# Control-MCU.net
KiCad netlist of a schematic drawn in Altium Designer
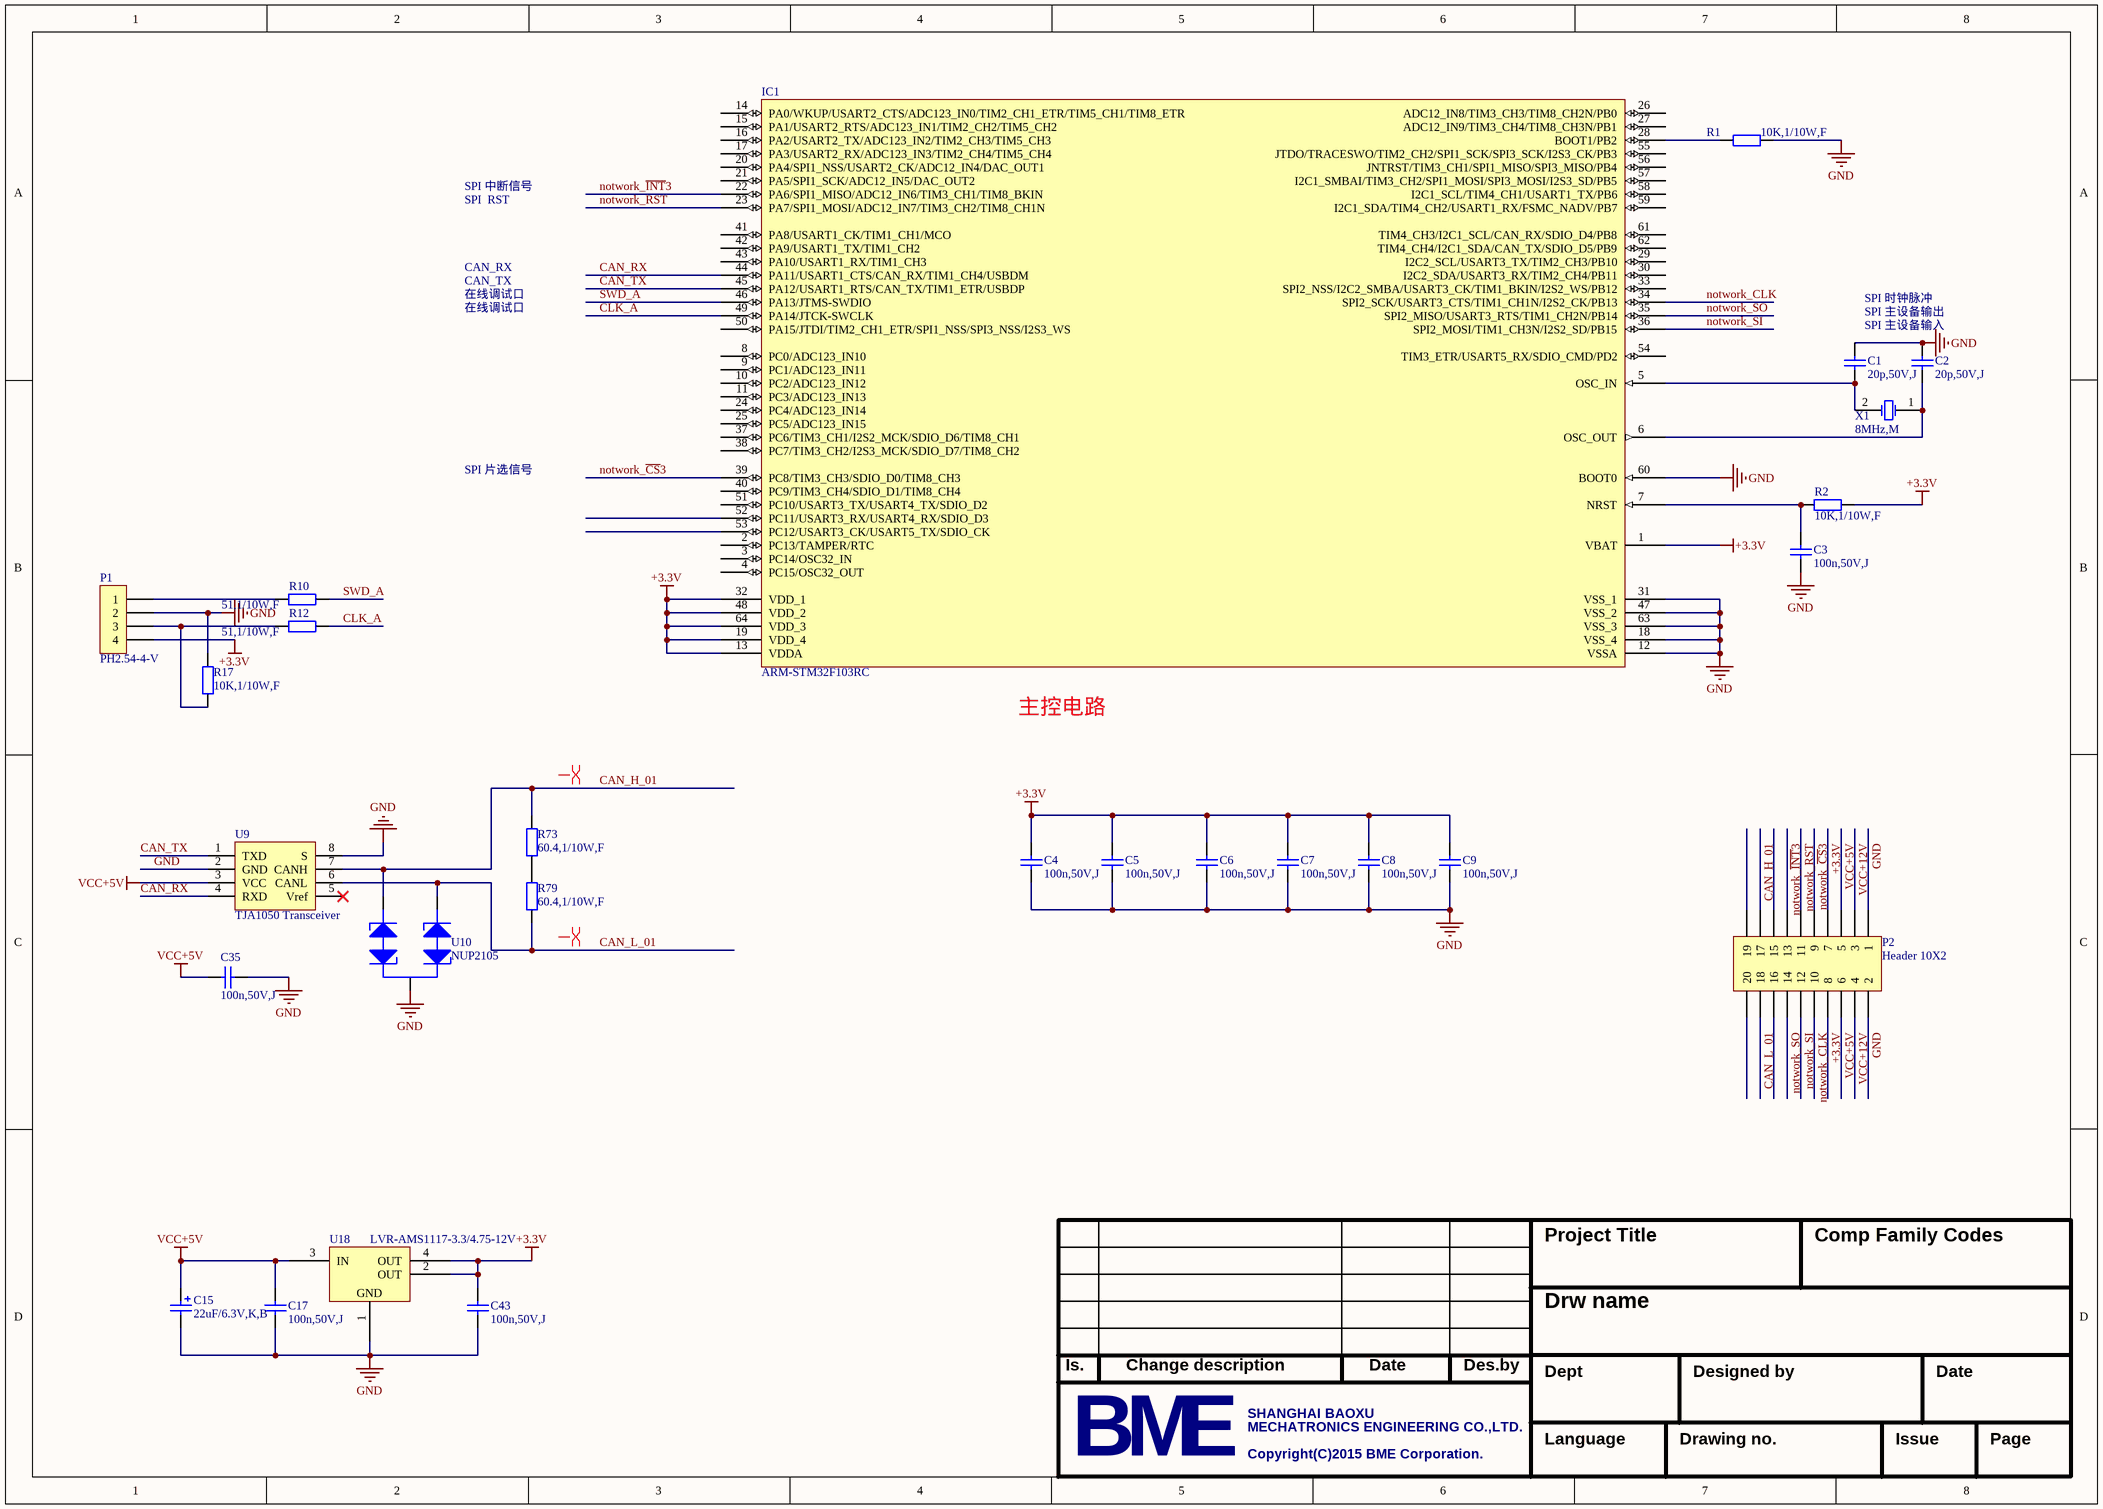
[diagram p0: Control-MCU.SchDoc]

(export (version "E")
  (design (tool "Eeschema 10.0.6"))
  (components
    (comp (ref "C1")
      (value "20p,50V,J")
      (footprint "C0603")
      (fields (field (name "PART NUMBER") "30602019"))
      (libsource (lib "KNLK-Chip Capacitors") (part "30602019"))
    )
    (comp (ref "C2")
      (value "20p,50V,J")
      (footprint "C0603")
      (fields (field (name "PART NUMBER") "30602019"))
      (libsource (lib "KNLK-Chip Capacitors") (part "30602019"))
    )
    (comp (ref "C3")
      (value "100n,50V,J")
      (footprint "C0603")
      (fields (field (name "PART NUMBER") "30602059"))
      (libsource (lib "KNLK-Chip Capacitors") (part "30602059"))
    )
    (comp (ref "C4")
      (value "100n,50V,J")
      (footprint "C0603")
      (fields (field (name "PART NUMBER") "30602059"))
      (libsource (lib "KNLK-Chip Capacitors") (part "30602059"))
    )
    (comp (ref "C5")
      (value "100n,50V,J")
      (footprint "C0603")
      (fields (field (name "PART NUMBER") "30602059"))
      (libsource (lib "KNLK-Chip Capacitors") (part "30602059"))
    )
    (comp (ref "C6")
      (value "100n,50V,J")
      (footprint "C0603")
      (fields (field (name "PART NUMBER") "30602059"))
      (libsource (lib "KNLK-Chip Capacitors") (part "30602059"))
    )
    (comp (ref "C7")
      (value "100n,50V,J")
      (footprint "C0603")
      (fields (field (name "PART NUMBER") "30602059"))
      (libsource (lib "KNLK-Chip Capacitors") (part "30602059"))
    )
    (comp (ref "C8")
      (value "100n,50V,J")
      (footprint "C0603")
      (fields (field (name "PART NUMBER") "30602059"))
      (libsource (lib "KNLK-Chip Capacitors") (part "30602059"))
    )
    (comp (ref "C9")
      (value "100n,50V,J")
      (footprint "C0603")
      (fields (field (name "PART NUMBER") "30602059"))
      (libsource (lib "KNLK-Chip Capacitors") (part "30602059"))
    )
    (comp (ref "C15")
      (value "22uF/6.3V,K,B")
      (footprint "3528B")
      (fields (field (name "PART NUMBER") "30603403"))
      (libsource (lib "KNLK-Tantalum Capacitor") (part "30603403"))
    )
    (comp (ref "C17")
      (value "100n,50V,J")
      (footprint "C0603")
      (fields (field (name "PART NUMBER") "30602059"))
      (libsource (lib "KNLK-Chip Capacitors") (part "30602059"))
    )
    (comp (ref "C35")
      (value "100n,50V,J")
      (footprint "C0603")
      (fields (field (name "PART NUMBER") "30602059"))
      (libsource (lib "KNLK-Chip Capacitors") (part "30602059"))
    )
    (comp (ref "C43")
      (value "100n,50V,J")
      (footprint "C0603")
      (fields (field (name "PART NUMBER") "30602059"))
      (libsource (lib "KNLK-Chip Capacitors") (part "30602059"))
    )
    (comp (ref "IC1")
      (value "ARM-STM32F103RC")
      (footprint "LQFP-64")
      (fields (field (name "PART NUMBER") "30613205"))
      (libsource (lib "KNLK-SMT chip") (part "30613205"))
    )
    (comp (ref "P1")
      (value "PH2.54-4-V")
      (footprint "SIP4")
      (fields (field (name "PART NUMBER") "30609103"))
      (libsource (lib "KNLK-Interface") (part "30609103"))
    )
    (comp (ref "P2")
      (value "Header 10X2")
      (footprint "805-1")
      (description "Header, 10-Pin, Dual row")
      (fields (field (name "PUBLISHER") "Altium Limited"))
      (libsource (lib "Miscellaneous Connectors") (part "Header 10X2"))
    )
    (comp (ref "R1")
      (value "10K,1/10W,F")
      (footprint "R0603")
      (fields (field (name "PART NUMBER") "30601099"))
      (libsource (lib "KNLK-Chip Resistor") (part "30601099"))
    )
    (comp (ref "R2")
      (value "10K,1/10W,F")
      (footprint "R0603")
      (fields (field (name "PART NUMBER") "30601099"))
      (libsource (lib "KNLK-Chip Resistor") (part "30601099"))
    )
    (comp (ref "R10")
      (value "51,1/10W,F")
      (footprint "R0603")
      (fields (field (name "PART NUMBER") "30601043"))
      (libsource (lib "KNLK-Chip Resistor") (part "30601043"))
    )
    (comp (ref "R12")
      (value "51,1/10W,F")
      (footprint "R0603")
      (fields (field (name "PART NUMBER") "30601043"))
      (libsource (lib "KNLK-Chip Resistor") (part "30601043"))
    )
    (comp (ref "R17")
      (value "10K,1/10W,F")
      (footprint "R0603")
      (fields (field (name "PART NUMBER") "30601099"))
      (libsource (lib "") (part "30601099_1"))
    )
    (comp (ref "R73")
      (value "60.4,1/10W,F")
      (footprint "R0603")
      (fields (field (name "PART NUMBER") "30601045"))
      (libsource (lib "KNLK-Chip Resistor") (part "30601045"))
    )
    (comp (ref "R79")
      (value "60.4,1/10W,F")
      (footprint "R0603")
      (fields (field (name "PART NUMBER") "30601045"))
      (libsource (lib "KNLK-Chip Resistor") (part "30601045"))
    )
    (comp (ref "U9")
      (value "TJA1050 Transceiver")
      (footprint "SOP-8")
      (fields (field (name "PART NUMBER") "30613501"))
      (libsource (lib "KNLK-SMT chip") (part "30613501"))
    )
    (comp (ref "U10")
      (value "NUP2105")
      (footprint "SOT-23P")
      (fields (field (name "PART NUMBER") "30613517"))
      (libsource (lib "KNLK-SMT chip") (part "30613517"))
    )
    (comp (ref "U18")
      (value "LVR-AMS1117-3.3/4.75-12V")
      (footprint "SOT-223")
      (fields (field (name "PART NUMBER") "30614001"))
      (libsource (lib "KNLK-Power supply chip") (part "30614001"))
    )
    (comp (ref "X1")
      (value "8MHz,M")
      (footprint "X5032")
      (fields (field (name "PART NUMBER") "30612002"))
      (libsource (lib "KNLK-CrystalOscillator") (part "30612002"))
    )
  )
  (nets
    (net (code "1") (name "+3.3V") (class "Default")
      (node (ref "C4") (pin "2") (pinfunction "2_2") (pintype "passive"))
      (node (ref "C43") (pin "1") (pinfunction "1_1") (pintype "passive"))
      (node (ref "C5") (pin "2") (pinfunction "2_2") (pintype "passive"))
      (node (ref "C6") (pin "2") (pinfunction "2_2") (pintype "passive"))
      (node (ref "C7") (pin "2") (pinfunction "2_2") (pintype "passive"))
      (node (ref "C8") (pin "2") (pinfunction "2_2") (pintype "passive"))
      (node (ref "C9") (pin "2") (pinfunction "2_2") (pintype "passive"))
      (node (ref "IC1") (pin "1") (pinfunction "VBAT_1") (pintype "power_in"))
      (node (ref "IC1") (pin "13") (pinfunction "VDDA_13") (pintype "power_in"))
      (node (ref "IC1") (pin "19") (pinfunction "VDD_4_19") (pintype "power_in"))
      (node (ref "IC1") (pin "32") (pinfunction "VDD_1_32") (pintype "power_in"))
      (node (ref "IC1") (pin "48") (pinfunction "VDD_2_48") (pintype "power_in"))
      (node (ref "IC1") (pin "64") (pinfunction "VDD_3_64") (pintype "power_in"))
      (node (ref "P1") (pin "4") (pinfunction "4_4") (pintype "passive"))
      (node (ref "P2") (pin "7") (pinfunction "7_7") (pintype "passive"))
      (node (ref "P2") (pin "8") (pinfunction "8_8") (pintype "passive"))
      (node (ref "R2") (pin "1") (pinfunction "1_1") (pintype "passive"))
      (node (ref "U18") (pin "2") (pinfunction "OUT_2") (pintype "passive"))
      (node (ref "U18") (pin "4") (pinfunction "OUT_4") (pintype "passive"))
    )
    (net (code "2") (name "/CAN_H_01") (class "Default")
      (node (ref "P2") (pin "17") (pinfunction "17_17") (pintype "passive"))
      (node (ref "R73") (pin "2") (pinfunction "2_2") (pintype "passive"))
      (node (ref "U10") (pin "1") (pinfunction "1_1") (pintype "passive"))
      (node (ref "U9") (pin "7") (pinfunction "CANH_7") (pintype "passive"))
    )
    (net (code "3") (name "/CAN_L_01") (class "Default")
      (node (ref "P2") (pin "18") (pinfunction "18_18") (pintype "passive"))
      (node (ref "R79") (pin "1") (pinfunction "1_1") (pintype "passive"))
      (node (ref "U10") (pin "2") (pinfunction "2_2") (pintype "passive"))
      (node (ref "U9") (pin "6") (pinfunction "CANL_6") (pintype "passive"))
    )
    (net (code "4") (name "/CAN_RX") (class "Default")
      (node (ref "IC1") (pin "44") (pinfunction "PA11/USART1_CTS/CAN_RX/TIM1_CH4/USBDM_44") (pintype "bidirectional"))
      (node (ref "U9") (pin "4") (pinfunction "RXD_4") (pintype "passive"))
    )
    (net (code "5") (name "/CAN_TX") (class "Default")
      (node (ref "IC1") (pin "45") (pinfunction "PA12/USART1_RTS/CAN_TX/TIM1_ETR/USBDP_45") (pintype "bidirectional"))
      (node (ref "U9") (pin "1") (pinfunction "TXD_1") (pintype "passive"))
    )
    (net (code "6") (name "/CLK_A") (class "Default")
      (node (ref "IC1") (pin "49") (pinfunction "PA14/JTCK-SWCLK_49") (pintype "bidirectional"))
      (node (ref "R12") (pin "2") (pinfunction "2_2") (pintype "passive"))
    )
    (net (code "7") (name "/SWD_A") (class "Default")
      (node (ref "IC1") (pin "46") (pinfunction "PA13/JTMS-SWDIO_46") (pintype "bidirectional"))
      (node (ref "R10") (pin "2") (pinfunction "2_2") (pintype "passive"))
    )
    (net (code "8") (name "/VCC+12V") (class "Default")
      (node (ref "P2") (pin "3") (pinfunction "3_3") (pintype "passive"))
      (node (ref "P2") (pin "4") (pinfunction "4_4") (pintype "passive"))
    )
    (net (code "9") (name "/notwork_CLK") (class "Default")
      (node (ref "IC1") (pin "34") (pinfunction "SPI2_SCK/USART3_CTS/TIM1_CH1N/I2S2_CK/PB13_34") (pintype "bidirectional"))
      (node (ref "P2") (pin "10") (pinfunction "10_10") (pintype "passive"))
    )
    (net (code "10") (name "/notwork_RST") (class "Default")
      (node (ref "IC1") (pin "23") (pinfunction "PA7/SPI1_MOSI/ADC12_IN7/TIM3_CH2/TIM8_CH1N_23") (pintype "bidirectional"))
      (node (ref "P2") (pin "11") (pinfunction "11_11") (pintype "passive"))
    )
    (net (code "11") (name "/notwork_SI") (class "Default")
      (node (ref "IC1") (pin "36") (pinfunction "SPI2_MOSI/TIM1_CH3N/I2S2_SD/PB15_36") (pintype "bidirectional"))
      (node (ref "P2") (pin "12") (pinfunction "12_12") (pintype "passive"))
    )
    (net (code "12") (name "/notwork_SO") (class "Default")
      (node (ref "IC1") (pin "35") (pinfunction "SPI2_MISO/USART3_RTS/TIM1_CH2N/PB14_35") (pintype "bidirectional"))
      (node (ref "P2") (pin "14") (pinfunction "14_14") (pintype "passive"))
    )
    (net (code "13") (name "/notwork_~{CS}3") (class "Default")
      (node (ref "IC1") (pin "39") (pinfunction "PC8/TIM3_CH3/SDIO_D0/TIM8_CH3_39") (pintype "bidirectional"))
      (node (ref "P2") (pin "9") (pinfunction "9_9") (pintype "passive"))
    )
    (net (code "14") (name "/notwork_~{INT}3") (class "Default")
      (node (ref "IC1") (pin "22") (pinfunction "PA6/SPI1_MISO/ADC12_IN6/TIM3_CH1/TIM8_BKIN_22") (pintype "bidirectional"))
      (node (ref "P2") (pin "13") (pinfunction "13_13") (pintype "passive"))
    )
    (net (code "15") (name "GND") (class "Default")
      (node (ref "C1") (pin "2") (pinfunction "2_2") (pintype "passive"))
      (node (ref "C15") (pin "2") (pinfunction "2_2") (pintype "passive"))
      (node (ref "C17") (pin "2") (pinfunction "2_2") (pintype "passive"))
      (node (ref "C2") (pin "2") (pinfunction "2_2") (pintype "passive"))
      (node (ref "C3") (pin "1") (pinfunction "1_1") (pintype "passive"))
      (node (ref "C35") (pin "1") (pinfunction "1_1") (pintype "passive"))
      (node (ref "C4") (pin "1") (pinfunction "1_1") (pintype "passive"))
      (node (ref "C43") (pin "2") (pinfunction "2_2") (pintype "passive"))
      (node (ref "C5") (pin "1") (pinfunction "1_1") (pintype "passive"))
      (node (ref "C6") (pin "1") (pinfunction "1_1") (pintype "passive"))
      (node (ref "C7") (pin "1") (pinfunction "1_1") (pintype "passive"))
      (node (ref "C8") (pin "1") (pinfunction "1_1") (pintype "passive"))
      (node (ref "C9") (pin "1") (pinfunction "1_1") (pintype "passive"))
      (node (ref "IC1") (pin "12") (pinfunction "VSSA_12") (pintype "power_in"))
      (node (ref "IC1") (pin "18") (pinfunction "VSS_4_18") (pintype "power_in"))
      (node (ref "IC1") (pin "31") (pinfunction "VSS_1_31") (pintype "power_in"))
      (node (ref "IC1") (pin "47") (pinfunction "VSS_2_47") (pintype "power_in"))
      (node (ref "IC1") (pin "60") (pinfunction "BOOT0_60") (pintype "input"))
      (node (ref "IC1") (pin "63") (pinfunction "VSS_3_63") (pintype "power_in"))
      (node (ref "P1") (pin "2") (pinfunction "2_2") (pintype "passive"))
      (node (ref "P2") (pin "1") (pinfunction "1_1") (pintype "passive"))
      (node (ref "P2") (pin "2") (pinfunction "2_2") (pintype "passive"))
      (node (ref "R1") (pin "1") (pinfunction "1_1") (pintype "passive"))
      (node (ref "R17") (pin "1") (pinfunction "1_1") (pintype "passive"))
      (node (ref "U10") (pin "3") (pinfunction "3_3") (pintype "passive"))
      (node (ref "U18") (pin "1") (pinfunction "GND_1") (pintype "passive"))
      (node (ref "U9") (pin "2") (pinfunction "GND_2") (pintype "passive"))
      (node (ref "U9") (pin "8") (pinfunction "S_8") (pintype "passive"))
    )
    (net (code "16") (name "Net-(IC1-BOOT1{slash}PB2)") (class "Default")
      (node (ref "IC1") (pin "28") (pinfunction "BOOT1/PB2_28") (pintype "bidirectional"))
      (node (ref "R1") (pin "2") (pinfunction "2_2") (pintype "passive"))
    )
    (net (code "17") (name "Net-(IC1-NRST)") (class "Default")
      (node (ref "C3") (pin "2") (pinfunction "2_2") (pintype "passive"))
      (node (ref "IC1") (pin "7") (pinfunction "NRST_7") (pintype "input"))
      (node (ref "R2") (pin "2") (pinfunction "2_2") (pintype "passive"))
    )
    (net (code "18") (name "Net-(IC1-OSC_IN)") (class "Default")
      (node (ref "C1") (pin "1") (pinfunction "1_1") (pintype "passive"))
      (node (ref "IC1") (pin "5") (pinfunction "OSC_IN_5") (pintype "input"))
      (node (ref "X1") (pin "2") (pinfunction "OSC2_2") (pintype "passive"))
    )
    (net (code "19") (name "Net-(IC1-OSC_OUT)") (class "Default")
      (node (ref "C2") (pin "1") (pinfunction "1_1") (pintype "passive"))
      (node (ref "IC1") (pin "6") (pinfunction "OSC_OUT_6") (pintype "output"))
      (node (ref "X1") (pin "1") (pinfunction "OSC1_1") (pintype "passive"))
    )
    (net (code "20") (name "Net-(P1-Pad1)") (class "Default")
      (node (ref "P1") (pin "1") (pinfunction "1_1") (pintype "passive"))
      (node (ref "R10") (pin "1") (pinfunction "1_1") (pintype "passive"))
    )
    (net (code "21") (name "Net-(P1-Pad3)") (class "Default")
      (node (ref "P1") (pin "3") (pinfunction "3_3") (pintype "passive"))
      (node (ref "R12") (pin "1") (pinfunction "1_1") (pintype "passive"))
      (node (ref "R17") (pin "2") (pinfunction "2_2") (pintype "passive"))
    )
    (net (code "22") (name "Net-(R73-Pad1)") (class "Default")
      (node (ref "R73") (pin "1") (pinfunction "1_1") (pintype "passive"))
      (node (ref "R79") (pin "2") (pinfunction "2_2") (pintype "passive"))
    )
    (net (code "23") (name "VCC+5V") (class "Default")
      (node (ref "C15") (pin "1") (pinfunction "1_1") (pintype "passive"))
      (node (ref "C17") (pin "1") (pinfunction "1_1") (pintype "passive"))
      (node (ref "C35") (pin "2") (pinfunction "2_2") (pintype "passive"))
      (node (ref "P2") (pin "5") (pinfunction "5_5") (pintype "passive"))
      (node (ref "P2") (pin "6") (pinfunction "6_6") (pintype "passive"))
      (node (ref "U18") (pin "3") (pinfunction "IN_3") (pintype "passive"))
      (node (ref "U9") (pin "3") (pinfunction "VCC_3") (pintype "passive"))
    )
    (net (code "24") (name "unconnected-(IC1-ADC12_IN8{slash}TIM3_CH3{slash}TIM8_CH2N{slash}PB0-Pad26)") (class "Default")
      (node (ref "IC1") (pin "26") (pinfunction "ADC12_IN8/TIM3_CH3/TIM8_CH2N/PB0_26") (pintype "bidirectional"))
    )
    (net (code "25") (name "unconnected-(IC1-ADC12_IN9{slash}TIM3_CH4{slash}TIM8_CH3N{slash}PB1-Pad27)") (class "Default")
      (node (ref "IC1") (pin "27") (pinfunction "ADC12_IN9/TIM3_CH4/TIM8_CH3N/PB1_27") (pintype "bidirectional"))
    )
    (net (code "26") (name "unconnected-(IC1-I2C1_SCL{slash}TIM4_CH1{slash}USART1_TX{slash}PB6-Pad58)") (class "Default")
      (node (ref "IC1") (pin "58") (pinfunction "I2C1_SCL/TIM4_CH1/USART1_TX/PB6_58") (pintype "bidirectional"))
    )
    (net (code "27") (name "unconnected-(IC1-I2C1_SDA{slash}TIM4_CH2{slash}USART1_RX{slash}FSMC_NADV{slash}PB7-Pad59)") (class "Default")
      (node (ref "IC1") (pin "59") (pinfunction "I2C1_SDA/TIM4_CH2/USART1_RX/FSMC_NADV/PB7_59") (pintype "bidirectional"))
    )
    (net (code "28") (name "unconnected-(IC1-I2C1_SMBAI{slash}TIM3_CH2{slash}SPI1_MOSI{slash}SPI3_MOSI{slash}I2S3_SD{slash}PB5-Pad57)") (class "Default")
      (node (ref "IC1") (pin "57") (pinfunction "I2C1_SMBAI/TIM3_CH2/SPI1_MOSI/SPI3_MOSI/I2S3_SD/PB5_57") (pintype "bidirectional"))
    )
    (net (code "29") (name "unconnected-(IC1-I2C2_SCL{slash}USART3_TX{slash}TIM2_CH3{slash}PB10-Pad29)") (class "Default")
      (node (ref "IC1") (pin "29") (pinfunction "I2C2_SCL/USART3_TX/TIM2_CH3/PB10_29") (pintype "bidirectional"))
    )
    (net (code "30") (name "unconnected-(IC1-I2C2_SDA{slash}USART3_RX{slash}TIM2_CH4{slash}PB11-Pad30)") (class "Default")
      (node (ref "IC1") (pin "30") (pinfunction "I2C2_SDA/USART3_RX/TIM2_CH4/PB11_30") (pintype "bidirectional"))
    )
    (net (code "31") (name "unconnected-(IC1-JNTRST{slash}TIM3_CH1{slash}SPI1_MISO{slash}SPI3_MISO{slash}PB4-Pad56)") (class "Default")
      (node (ref "IC1") (pin "56") (pinfunction "JNTRST/TIM3_CH1/SPI1_MISO/SPI3_MISO/PB4_56") (pintype "bidirectional"))
    )
    (net (code "32") (name "unconnected-(IC1-JTDO{slash}TRACESWO{slash}TIM2_CH2{slash}SPI1_SCK{slash}SPI3_SCK{slash}I2S3_CK{slash}PB3-Pad55)") (class "Default")
      (node (ref "IC1") (pin "55") (pinfunction "JTDO/TRACESWO/TIM2_CH2/SPI1_SCK/SPI3_SCK/I2S3_CK/PB3_55") (pintype "bidirectional"))
    )
    (net (code "33") (name "unconnected-(IC1-PA0{slash}WKUP{slash}USART2_CTS{slash}ADC123_IN0{slash}TIM2_CH1_ETR{slash}TIM5_CH1{slash}TIM8_ETR-Pad14)") (class "Default")
      (node (ref "IC1") (pin "14") (pinfunction "PA0/WKUP/USART2_CTS/ADC123_IN0/TIM2_CH1_ETR/TIM5_CH1/TIM8_ETR_14") (pintype "bidirectional"))
    )
    (net (code "34") (name "unconnected-(IC1-PA1{slash}USART2_RTS{slash}ADC123_IN1{slash}TIM2_CH2{slash}TIM5_CH2-Pad15)") (class "Default")
      (node (ref "IC1") (pin "15") (pinfunction "PA1/USART2_RTS/ADC123_IN1/TIM2_CH2/TIM5_CH2_15") (pintype "bidirectional"))
    )
    (net (code "35") (name "unconnected-(IC1-PA2{slash}USART2_TX{slash}ADC123_IN2{slash}TIM2_CH3{slash}TIM5_CH3-Pad16)") (class "Default")
      (node (ref "IC1") (pin "16") (pinfunction "PA2/USART2_TX/ADC123_IN2/TIM2_CH3/TIM5_CH3_16") (pintype "bidirectional"))
    )
    (net (code "36") (name "unconnected-(IC1-PA3{slash}USART2_RX{slash}ADC123_IN3{slash}TIM2_CH4{slash}TIM5_CH4-Pad17)") (class "Default")
      (node (ref "IC1") (pin "17") (pinfunction "PA3/USART2_RX/ADC123_IN3/TIM2_CH4/TIM5_CH4_17") (pintype "bidirectional"))
    )
    (net (code "37") (name "unconnected-(IC1-PA4{slash}SPI1_NSS{slash}USART2_CK{slash}ADC12_IN4{slash}DAC_OUT1-Pad20)") (class "Default")
      (node (ref "IC1") (pin "20") (pinfunction "PA4/SPI1_NSS/USART2_CK/ADC12_IN4/DAC_OUT1_20") (pintype "bidirectional"))
    )
    (net (code "38") (name "unconnected-(IC1-PA5{slash}SPI1_SCK{slash}ADC12_IN5{slash}DAC_OUT2-Pad21)") (class "Default")
      (node (ref "IC1") (pin "21") (pinfunction "PA5/SPI1_SCK/ADC12_IN5/DAC_OUT2_21") (pintype "bidirectional"))
    )
    (net (code "39") (name "unconnected-(IC1-PA8{slash}USART1_CK{slash}TIM1_CH1{slash}MCO-Pad41)") (class "Default")
      (node (ref "IC1") (pin "41") (pinfunction "PA8/USART1_CK/TIM1_CH1/MCO_41") (pintype "bidirectional"))
    )
    (net (code "40") (name "unconnected-(IC1-PA9{slash}USART1_TX{slash}TIM1_CH2-Pad42)") (class "Default")
      (node (ref "IC1") (pin "42") (pinfunction "PA9/USART1_TX/TIM1_CH2_42") (pintype "bidirectional"))
    )
    (net (code "41") (name "unconnected-(IC1-PA10{slash}USART1_RX{slash}TIM1_CH3-Pad43)") (class "Default")
      (node (ref "IC1") (pin "43") (pinfunction "PA10/USART1_RX/TIM1_CH3_43") (pintype "bidirectional"))
    )
    (net (code "42") (name "unconnected-(IC1-PA15{slash}JTDI{slash}TIM2_CH1_ETR{slash}SPI1_NSS{slash}SPI3_NSS{slash}I2S3_WS-Pad50)") (class "Default")
      (node (ref "IC1") (pin "50") (pinfunction "PA15/JTDI/TIM2_CH1_ETR/SPI1_NSS/SPI3_NSS/I2S3_WS_50") (pintype "bidirectional"))
    )
    (net (code "43") (name "unconnected-(IC1-PC0{slash}ADC123_IN10-Pad8)") (class "Default")
      (node (ref "IC1") (pin "8") (pinfunction "PC0/ADC123_IN10_8") (pintype "bidirectional"))
    )
    (net (code "44") (name "unconnected-(IC1-PC1{slash}ADC123_IN11-Pad9)") (class "Default")
      (node (ref "IC1") (pin "9") (pinfunction "PC1/ADC123_IN11_9") (pintype "bidirectional"))
    )
    (net (code "45") (name "unconnected-(IC1-PC2{slash}ADC123_IN12-Pad10)") (class "Default")
      (node (ref "IC1") (pin "10") (pinfunction "PC2/ADC123_IN12_10") (pintype "bidirectional"))
    )
    (net (code "46") (name "unconnected-(IC1-PC3{slash}ADC123_IN13-Pad11)") (class "Default")
      (node (ref "IC1") (pin "11") (pinfunction "PC3/ADC123_IN13_11") (pintype "bidirectional"))
    )
    (net (code "47") (name "unconnected-(IC1-PC4{slash}ADC123_IN14-Pad24)") (class "Default")
      (node (ref "IC1") (pin "24") (pinfunction "PC4/ADC123_IN14_24") (pintype "bidirectional"))
    )
    (net (code "48") (name "unconnected-(IC1-PC5{slash}ADC123_IN15-Pad25)") (class "Default")
      (node (ref "IC1") (pin "25") (pinfunction "PC5/ADC123_IN15_25") (pintype "bidirectional"))
    )
    (net (code "49") (name "unconnected-(IC1-PC6{slash}TIM3_CH1{slash}I2S2_MCK{slash}SDIO_D6{slash}TIM8_CH1-Pad37)") (class "Default")
      (node (ref "IC1") (pin "37") (pinfunction "PC6/TIM3_CH1/I2S2_MCK/SDIO_D6/TIM8_CH1_37") (pintype "bidirectional"))
    )
    (net (code "50") (name "unconnected-(IC1-PC7{slash}TIM3_CH2{slash}I2S3_MCK{slash}SDIO_D7{slash}TIM8_CH2-Pad38)") (class "Default")
      (node (ref "IC1") (pin "38") (pinfunction "PC7/TIM3_CH2/I2S3_MCK/SDIO_D7/TIM8_CH2_38") (pintype "bidirectional"))
    )
    (net (code "51") (name "unconnected-(IC1-PC9{slash}TIM3_CH4{slash}SDIO_D1{slash}TIM8_CH4-Pad40)") (class "Default")
      (node (ref "IC1") (pin "40") (pinfunction "PC9/TIM3_CH4/SDIO_D1/TIM8_CH4_40") (pintype "bidirectional"))
    )
    (net (code "52") (name "unconnected-(IC1-PC10{slash}USART3_TX{slash}USART4_TX{slash}SDIO_D2-Pad51)") (class "Default")
      (node (ref "IC1") (pin "51") (pinfunction "PC10/USART3_TX/USART4_TX/SDIO_D2_51") (pintype "bidirectional"))
    )
    (net (code "53") (name "unconnected-(IC1-PC11{slash}USART3_RX{slash}USART4_RX{slash}SDIO_D3-Pad52)") (class "Default")
      (node (ref "IC1") (pin "52") (pinfunction "PC11/USART3_RX/USART4_RX/SDIO_D3_52") (pintype "bidirectional"))
    )
    (net (code "54") (name "unconnected-(IC1-PC12{slash}USART3_CK{slash}USART5_TX{slash}SDIO_CK-Pad53)") (class "Default")
      (node (ref "IC1") (pin "53") (pinfunction "PC12/USART3_CK/USART5_TX/SDIO_CK_53") (pintype "bidirectional"))
    )
    (net (code "55") (name "unconnected-(IC1-PC13{slash}TAMPER{slash}RTC-Pad2)") (class "Default")
      (node (ref "IC1") (pin "2") (pinfunction "PC13/TAMPER/RTC_2") (pintype "bidirectional"))
    )
    (net (code "56") (name "unconnected-(IC1-PC14{slash}OSC32_IN-Pad3)") (class "Default")
      (node (ref "IC1") (pin "3") (pinfunction "PC14/OSC32_IN_3") (pintype "bidirectional"))
    )
    (net (code "57") (name "unconnected-(IC1-PC15{slash}OSC32_OUT-Pad4)") (class "Default")
      (node (ref "IC1") (pin "4") (pinfunction "PC15/OSC32_OUT_4") (pintype "bidirectional"))
    )
    (net (code "58") (name "unconnected-(IC1-SPI2_NSS{slash}I2C2_SMBA{slash}USART3_CK{slash}TIM1_BKIN{slash}I2S2_WS{slash}PB12-Pad33)") (class "Default")
      (node (ref "IC1") (pin "33") (pinfunction "SPI2_NSS/I2C2_SMBA/USART3_CK/TIM1_BKIN/I2S2_WS/PB12_33") (pintype "bidirectional"))
    )
    (net (code "59") (name "unconnected-(IC1-TIM3_ETR{slash}USART5_RX{slash}SDIO_CMD{slash}PD2-Pad54)") (class "Default")
      (node (ref "IC1") (pin "54") (pinfunction "TIM3_ETR/USART5_RX/SDIO_CMD/PD2_54") (pintype "bidirectional"))
    )
    (net (code "60") (name "unconnected-(IC1-TIM4_CH3{slash}I2C1_SCL{slash}CAN_RX{slash}SDIO_D4{slash}PB8-Pad61)") (class "Default")
      (node (ref "IC1") (pin "61") (pinfunction "TIM4_CH3/I2C1_SCL/CAN_RX/SDIO_D4/PB8_61") (pintype "bidirectional"))
    )
    (net (code "61") (name "unconnected-(IC1-TIM4_CH4{slash}I2C1_SDA{slash}CAN_TX{slash}SDIO_D5{slash}PB9-Pad62)") (class "Default")
      (node (ref "IC1") (pin "62") (pinfunction "TIM4_CH4/I2C1_SDA/CAN_TX/SDIO_D5/PB9_62") (pintype "bidirectional"))
    )
    (net (code "62") (name "unconnected-(P2-Pad15)") (class "Default")
      (node (ref "P2") (pin "15") (pinfunction "15_15") (pintype "passive"))
    )
    (net (code "63") (name "unconnected-(P2-Pad16)") (class "Default")
      (node (ref "P2") (pin "16") (pinfunction "16_16") (pintype "passive"))
    )
    (net (code "64") (name "unconnected-(P2-Pad19)") (class "Default")
      (node (ref "P2") (pin "19") (pinfunction "19_19") (pintype "passive"))
    )
    (net (code "65") (name "unconnected-(P2-Pad20)") (class "Default")
      (node (ref "P2") (pin "20") (pinfunction "20_20") (pintype "passive"))
    )
    (net (code "66") (name "unconnected-(U9-Vref-Pad5)") (class "Default")
      (node (ref "U9") (pin "5") (pinfunction "Vref_5") (pintype "passive+no_connect"))
    )
  )
)
